# VoltageRegulator.net
KiCad netlist of a schematic drawn in Altium Designer
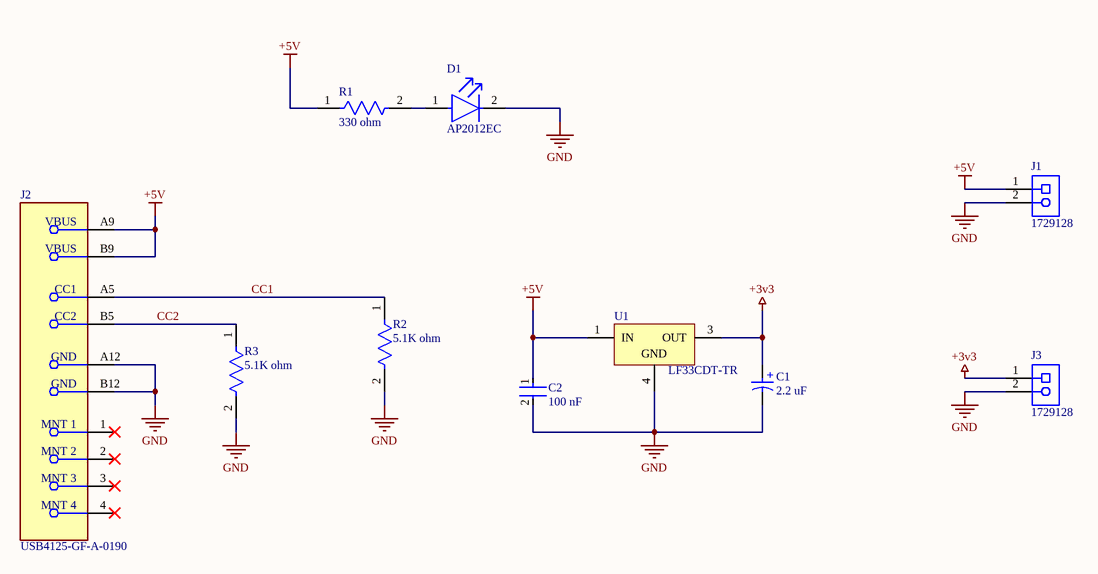
[diagram p0: VoltageRegulator.SchDoc]

(export (version "E")
  (design (tool "Eeschema 10.0.6"))
  (components
    (comp (ref "C1")
      (value "2.2 uF")
      (footprint "WCAP-ASLI_D4H5.5")
      (description "865080640002 WCAP-ASLI Aluminum Electrolytic Capacitors")
      (fields (field (name "TOLERANCE") "20%"))
      (libsource (lib "Altium Content Vault") (part "Capacitor_Polarized"))
    )
    (comp (ref "C2")
      (value "100 nF")
      (footprint "FP-C0805C-DN-MFG")
      (description "CAP CER 0.1UF 50V X7R 0805")
      (fields (field (name "TOLERANCE") "0.2") (field (name "MANUFACTURER PART NUMBER") "C0805C104M5RACTU"))
      (libsource (lib "Altium Content Vault") (part "b4654b650e69147ec39a6b967a45e02"))
    )
    (comp (ref "D1")
      (value "AP2012EC")
      (footprint "FP-AP2012EC-MFG")
      (description "LED RED CLEAR SMD")
      (libsource (lib "Altium Content Vault") (part "ab1c01a81903e929fc6c44469aada92"))
    )
    (comp (ref "J1")
      (value "1729128")
      (footprint "PHOE-1729128-2_V")
      (description "PCB Terminal Block, 13.5 A, 400 V, 2-Pin THD, RoHS, Bulk")
      (fields (field (name "MANUFACTURER") "Phoenix Contact"))
      (libsource (lib "Altium Content Vault") (part "CN-2P-F-R2"))
    )
    (comp (ref "J2")
      (value "USB4125-GF-A-0190")
      (footprint "FP-USB4125-GF-A-0190-MFG")
      (description "CONN RCPT TYPE C 6P SMD RA")
      (libsource (lib "Altium Content Vault") (part "a055484d46e58b234844902c9fd883a"))
    )
    (comp (ref "J3")
      (value "1729128")
      (footprint "PHOE-1729128-2_V")
      (description "PCB Terminal Block, 13.5 A, 400 V, 2-Pin THD, RoHS, Bulk")
      (fields (field (name "MANUFACTURER") "Phoenix Contact"))
      (libsource (lib "Altium Content Vault") (part "CN-2P-F-R2"))
    )
    (comp (ref "R1")
      (value "330 ohm")
      (footprint "FP-RT0805-MFG")
      (description "RES SMD 604K OHM 0.1% 1/8W 0805")
      (fields
        (field (name "OCTOPART") "https://octopart.com/rt0805brd07604kl-yageo-1479051")
        (field (name "TOLERANCE") "0.0025")
      )
      (libsource (lib "Altium Content Vault") (part "1029c3af85768c4190bb7ad29bc67b5"))
    )
    (comp (ref "R2")
      (value "5.1K ohm")
      (footprint "FP-RT0805-MFG")
      (description "RES SMD 604K OHM 0.1% 1/8W 0805")
      (fields
        (field (name "OCTOPART") "https://octopart.com/rt0805brd07604kl-yageo-1479051")
        (field (name "TOLERANCE") "0.0025")
      )
      (libsource (lib "Altium Content Vault") (part "1029c3af85768c4190bb7ad29bc67b5"))
    )
    (comp (ref "R3")
      (value "5.1K ohm")
      (footprint "FP-RT0805-MFG")
      (description "RES SMD 604K OHM 0.1% 1/8W 0805")
      (fields
        (field (name "OCTOPART") "https://octopart.com/rt0805brd07604kl-yageo-1479051")
        (field (name "TOLERANCE") "0.0025")
      )
      (libsource (lib "Altium Content Vault") (part "1029c3af85768c4190bb7ad29bc67b5"))
    )
    (comp (ref "U1")
      (value "LF33CDT-TR")
      (footprint "TO-252_N")
      (description "500mA, Very Low Drop (0.45V) Voltage Regulator, 3.3V, 3-Pin DPAK, Tape and Reel")
      (libsource (lib "Altium Content Vault") (part "PM-REG-L4940-SOT3"))
    )
  )
  (nets
    (net (code "1") (name "+3v3") (class "Default")
      (node (ref "C1") (pin "1") (pinfunction "P_1") (pintype "passive"))
      (node (ref "J3") (pin "1") (pinfunction "1_1") (pintype "passive"))
      (node (ref "U1") (pin "3") (pinfunction "OUT_3") (pintype "power_in"))
    )
    (net (code "2") (name "+5V") (class "Default")
      (node (ref "C2") (pin "1") (pinfunction "1_1") (pintype "passive"))
      (node (ref "J1") (pin "1") (pinfunction "1_1") (pintype "passive"))
      (node (ref "J2") (pin "A9") (pinfunction "VBUS_A9") (pintype "passive"))
      (node (ref "J2") (pin "B9") (pinfunction "VBUS_B9") (pintype "passive"))
      (node (ref "R1") (pin "1") (pinfunction "1_1") (pintype "passive"))
      (node (ref "U1") (pin "1") (pinfunction "IN_1") (pintype "power_in"))
    )
    (net (code "3") (name "/CC1") (class "Default")
      (node (ref "J2") (pin "A5") (pinfunction "CC1_A5") (pintype "passive"))
      (node (ref "R2") (pin "1") (pinfunction "1_1") (pintype "passive"))
    )
    (net (code "4") (name "/CC2") (class "Default")
      (node (ref "J2") (pin "B5") (pinfunction "CC2_B5") (pintype "passive"))
      (node (ref "R3") (pin "1") (pinfunction "1_1") (pintype "passive"))
    )
    (net (code "5") (name "GND") (class "Default")
      (node (ref "C1") (pin "2") (pinfunction "N_2") (pintype "passive"))
      (node (ref "C2") (pin "2") (pinfunction "2_2") (pintype "passive"))
      (node (ref "D1") (pin "2") (pinfunction "C_2") (pintype "passive"))
      (node (ref "J1") (pin "2") (pinfunction "2_2") (pintype "passive"))
      (node (ref "J2") (pin "A12") (pinfunction "GND_A12") (pintype "passive"))
      (node (ref "J2") (pin "B12") (pinfunction "GND_B12") (pintype "passive"))
      (node (ref "J3") (pin "2") (pinfunction "2_2") (pintype "passive"))
      (node (ref "R2") (pin "2") (pinfunction "2_2") (pintype "passive"))
      (node (ref "R3") (pin "2") (pinfunction "2_2") (pintype "passive"))
      (node (ref "U1") (pin "4") (pinfunction "GND_4") (pintype "power_in"))
    )
    (net (code "6") (name "Net-(D1-A)") (class "Default")
      (node (ref "D1") (pin "1") (pinfunction "A_1") (pintype "passive"))
      (node (ref "R1") (pin "2") (pinfunction "2_2") (pintype "passive"))
    )
    (net (code "7") (name "unconnected-(J2-MNT_1-Pad1)") (class "Default")
      (node (ref "J2") (pin "1") (pinfunction "MNT_1_1") (pintype "passive+no_connect"))
    )
    (net (code "8") (name "unconnected-(J2-MNT_2-Pad2)") (class "Default")
      (node (ref "J2") (pin "2") (pinfunction "MNT_2_2") (pintype "passive+no_connect"))
    )
    (net (code "9") (name "unconnected-(J2-MNT_3-Pad3)") (class "Default")
      (node (ref "J2") (pin "3") (pinfunction "MNT_3_3") (pintype "passive+no_connect"))
    )
    (net (code "10") (name "unconnected-(J2-MNT_4-Pad4)") (class "Default")
      (node (ref "J2") (pin "4") (pinfunction "MNT_4_4") (pintype "passive+no_connect"))
    )
  )
)
